# avr_pcb.net
KiCad netlist of a schematic drawn in EAGLE
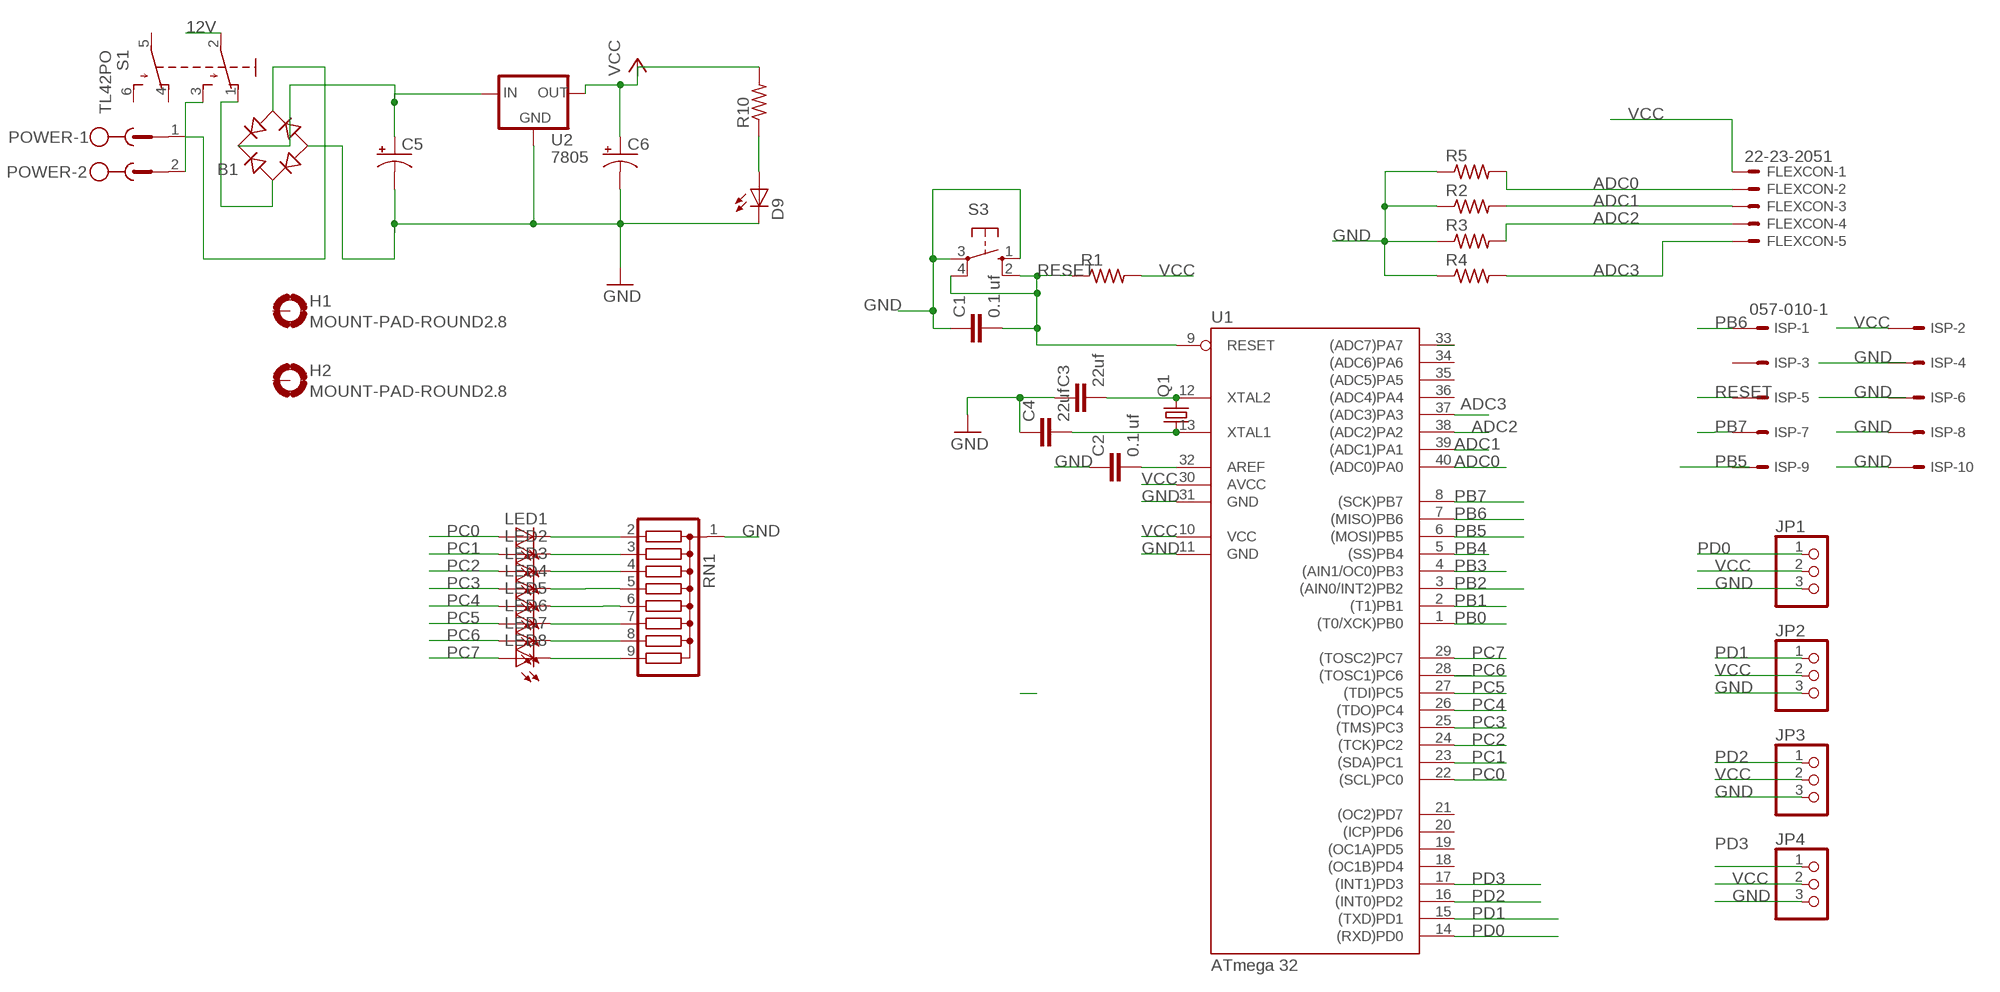
[diagram p0: schematic, sheet 1]

(export (version "E")
  (design (tool "Eeschema 10.0.6"))
  (components
    (comp (ref "B1")
      (value "RB1A")
      (footprint "eagle-import:RB1A")
      (libsource (lib "eagle-import") (part "RB1A"))
    )
    (comp (ref "C1")
      (value "0.1 uf")
      (footprint "eagle-import:C025-024X044")
      (libsource (lib "eagle-import") (part "C-EU025-024X044"))
    )
    (comp (ref "C2")
      (value "0.1 uf")
      (footprint "eagle-import:C025-024X044")
      (libsource (lib "eagle-import") (part "C-EU025-024X044"))
    )
    (comp (ref "C3")
      (value "22uf")
      (footprint "eagle-import:C025-024X044")
      (libsource (lib "eagle-import") (part "C-EU025-024X044"))
    )
    (comp (ref "C4")
      (value "22uf")
      (footprint "eagle-import:C025-024X044")
      (libsource (lib "eagle-import") (part "C-EU025-024X044"))
    )
    (comp (ref "C5")
      (value "CPOL-USE5-6")
      (footprint "eagle-import:E5-6")
      (libsource (lib "eagle-import") (part "CPOL-USE5-6"))
    )
    (comp (ref "C6")
      (value "CPOL-USE5-6")
      (footprint "eagle-import:E5-6")
      (libsource (lib "eagle-import") (part "CPOL-USE5-6"))
    )
    (comp (ref "D9")
      (value "LED3MM")
      (footprint "eagle-import:LED3MM")
      (libsource (lib "eagle-import") (part "LED3MM"))
    )
    (comp (ref "FLEXCON")
      (value "22-23-2051")
      (footprint "eagle-import:22-23-2051")
      (fields (field (name "MF") "MOLEX"))
      (libsource (lib "eagle-import") (part "22-23-2051"))
    )
    (comp (ref "H1")
      (value "MOUNT-PAD-ROUND2.8")
      (footprint "eagle-import:2,8-PAD")
      (libsource (lib "eagle-import") (part "MOUNT-PAD-ROUND2.8"))
    )
    (comp (ref "H2")
      (value "MOUNT-PAD-ROUND2.8")
      (footprint "eagle-import:2,8-PAD")
      (libsource (lib "eagle-import") (part "MOUNT-PAD-ROUND2.8"))
    )
    (comp (ref "ISP")
      (value "057-010-1")
      (footprint "eagle-import:057-010-1")
      (libsource (lib "eagle-import") (part "057-010-1"))
    )
    (comp (ref "JP1")
      (value "PINHD-1X3")
      (footprint "eagle-import:1X03")
      (fields (field (name "SPICEPREFIX") "J"))
      (libsource (lib "eagle-import") (part "PINHD-1X3"))
    )
    (comp (ref "JP2")
      (value "PINHD-1X3")
      (footprint "eagle-import:1X03")
      (libsource (lib "eagle-import") (part "PINHD-1X3"))
    )
    (comp (ref "JP3")
      (value "PINHD-1X3")
      (footprint "eagle-import:1X03")
      (libsource (lib "eagle-import") (part "PINHD-1X3"))
    )
    (comp (ref "JP4")
      (value "PINHD-1X3")
      (footprint "eagle-import:1X03")
      (libsource (lib "eagle-import") (part "PINHD-1X3"))
    )
    (comp (ref "LED1")
      (value "LED3MM")
      (footprint "eagle-import:LED3MM")
      (libsource (lib "eagle-import") (part "LED3MM"))
    )
    (comp (ref "LED2")
      (value "LED3MM")
      (footprint "eagle-import:LED3MM")
      (libsource (lib "eagle-import") (part "LED3MM"))
    )
    (comp (ref "LED3")
      (value "LED3MM")
      (footprint "eagle-import:LED3MM")
      (libsource (lib "eagle-import") (part "LED3MM"))
    )
    (comp (ref "LED4")
      (value "LED3MM")
      (footprint "eagle-import:LED3MM")
      (libsource (lib "eagle-import") (part "LED3MM"))
    )
    (comp (ref "LED5")
      (value "LED3MM")
      (footprint "eagle-import:LED3MM")
      (libsource (lib "eagle-import") (part "LED3MM"))
    )
    (comp (ref "LED6")
      (value "LED3MM")
      (footprint "eagle-import:LED3MM")
      (libsource (lib "eagle-import") (part "LED3MM"))
    )
    (comp (ref "LED7")
      (value "LED3MM")
      (footprint "eagle-import:LED3MM")
      (libsource (lib "eagle-import") (part "LED3MM"))
    )
    (comp (ref "LED8")
      (value "LED3MM")
      (footprint "eagle-import:LED3MM")
      (libsource (lib "eagle-import") (part "LED3MM"))
    )
    (comp (ref "POWER")
      (value "MSTBV2")
      (footprint "eagle-import:MSTBV2")
      (libsource (lib "eagle-import") (part "MSTBV2"))
    )
    (comp (ref "Q1")
      (value "CRYSTALHC18U-V")
      (footprint "eagle-import:HC18U-V")
      (libsource (lib "eagle-import") (part "CRYSTALHC18U-V"))
    )
    (comp (ref "R1")
      (value "R-US_0204/7")
      (footprint "eagle-import:0204_7")
      (libsource (lib "eagle-import") (part "R-US_0204/7"))
    )
    (comp (ref "R2")
      (value "R-US_0204/7")
      (footprint "eagle-import:0204_7")
      (libsource (lib "eagle-import") (part "R-US_0204/7"))
    )
    (comp (ref "R3")
      (value "R-US_0204/7")
      (footprint "eagle-import:0204_7")
      (libsource (lib "eagle-import") (part "R-US_0204/7"))
    )
    (comp (ref "R4")
      (value "R-US_0204/7")
      (footprint "eagle-import:0204_7")
      (libsource (lib "eagle-import") (part "R-US_0204/7"))
    )
    (comp (ref "R5")
      (value "R-US_0204/7")
      (footprint "eagle-import:0204_7")
      (libsource (lib "eagle-import") (part "R-US_0204/7"))
    )
    (comp (ref "R10")
      (value "R-US_0204/7")
      (footprint "eagle-import:0204_7")
      (libsource (lib "eagle-import") (part "R-US_0204/7"))
    )
    (comp (ref "RN1")
      (value "G08R")
      (footprint "eagle-import:SIL9")
      (libsource (lib "eagle-import") (part "G08R"))
    )
    (comp (ref "S1")
      (value "TL42PO")
      (footprint "eagle-import:TL4XPO")
      (libsource (lib "eagle-import") (part "TL42PO"))
    )
    (comp (ref "S3")
      (value "10-XX")
      (footprint "eagle-import:B3F-10XX")
      (fields (field (name "MPN") "B3F-1000"))
      (libsource (lib "eagle-import") (part "10-XX"))
    )
    (comp (ref "U1")
      (value "ATmega 32")
      (footprint "eagle-import:DIL40")
      (fields (field (name "MPN") "ATMEGA32-16PU"))
      (libsource (lib "eagle-import") (part "MEGA32-P"))
    )
    (comp (ref "U2")
      (value "7805")
      (footprint "eagle-import:78XXL")
      (libsource (lib "eagle-import") (part "78XXL"))
    )
  )
  (nets
    (net (code "1") (name "/12V") (class "Default")
      (node (ref "S1") (pin "2") (pinfunction "P_2") (pintype "passive"))
    )
    (net (code "2") (name "/ADC0") (class "Default")
      (node (ref "FLEXCON") (pin "2") (pinfunction "S_2") (pintype "passive"))
      (node (ref "R5") (pin "2") (pinfunction "2_2") (pintype "passive"))
      (node (ref "U1") (pin "40") (pinfunction "(ADC0)PA0_40") (pintype "bidirectional"))
    )
    (net (code "3") (name "/ADC1") (class "Default")
      (node (ref "FLEXCON") (pin "3") (pinfunction "S_3") (pintype "passive"))
      (node (ref "R2") (pin "2") (pinfunction "2_2") (pintype "passive"))
      (node (ref "U1") (pin "39") (pinfunction "(ADC1)PA1_39") (pintype "bidirectional"))
    )
    (net (code "4") (name "/ADC2") (class "Default")
      (node (ref "FLEXCON") (pin "4") (pinfunction "S_4") (pintype "passive"))
      (node (ref "R3") (pin "2") (pinfunction "2_2") (pintype "passive"))
      (node (ref "U1") (pin "38") (pinfunction "(ADC2)PA2_38") (pintype "bidirectional"))
    )
    (net (code "5") (name "/ADC3") (class "Default")
      (node (ref "FLEXCON") (pin "5") (pinfunction "S_5") (pintype "passive"))
      (node (ref "R4") (pin "2") (pinfunction "2_2") (pintype "passive"))
      (node (ref "U1") (pin "37") (pinfunction "(ADC3)PA3_37") (pintype "bidirectional"))
    )
    (net (code "6") (name "/PB0") (class "Default")
      (node (ref "U1") (pin "1") (pinfunction "(T0/XCK)PB0_1") (pintype "bidirectional"))
    )
    (net (code "7") (name "/PB1") (class "Default")
      (node (ref "U1") (pin "2") (pinfunction "(T1)PB1_2") (pintype "bidirectional"))
    )
    (net (code "8") (name "/PB2") (class "Default")
      (node (ref "U1") (pin "3") (pinfunction "(AIN0/INT2)PB2_3") (pintype "bidirectional"))
    )
    (net (code "9") (name "/PB3") (class "Default")
      (node (ref "U1") (pin "4") (pinfunction "(AIN1/OC0)PB3_4") (pintype "bidirectional"))
    )
    (net (code "10") (name "/PB4") (class "Default")
      (node (ref "U1") (pin "5") (pinfunction "(SS)PB4_5") (pintype "bidirectional"))
    )
    (net (code "11") (name "/PB5") (class "Default")
      (node (ref "ISP") (pin "9") (pinfunction "S_9") (pintype "passive"))
      (node (ref "U1") (pin "6") (pinfunction "(MOSI)PB5_6") (pintype "bidirectional"))
    )
    (net (code "12") (name "/PB6") (class "Default")
      (node (ref "ISP") (pin "1") (pinfunction "S_1") (pintype "passive"))
      (node (ref "U1") (pin "7") (pinfunction "(MISO)PB6_7") (pintype "bidirectional"))
    )
    (net (code "13") (name "/PB7") (class "Default")
      (node (ref "ISP") (pin "7") (pinfunction "S_7") (pintype "passive"))
      (node (ref "U1") (pin "8") (pinfunction "(SCK)PB7_8") (pintype "bidirectional"))
    )
    (net (code "14") (name "/PC0") (class "Default")
      (node (ref "LED1") (pin "A") (pinfunction "A_A") (pintype "passive"))
      (node (ref "U1") (pin "22") (pinfunction "(SCL)PC0_22") (pintype "bidirectional"))
    )
    (net (code "15") (name "/PC1") (class "Default")
      (node (ref "LED2") (pin "A") (pinfunction "A_A") (pintype "passive"))
      (node (ref "U1") (pin "23") (pinfunction "(SDA)PC1_23") (pintype "bidirectional"))
    )
    (net (code "16") (name "/PC2") (class "Default")
      (node (ref "LED3") (pin "A") (pinfunction "A_A") (pintype "passive"))
      (node (ref "U1") (pin "24") (pinfunction "(TCK)PC2_24") (pintype "bidirectional"))
    )
    (net (code "17") (name "/PC3") (class "Default")
      (node (ref "LED4") (pin "A") (pinfunction "A_A") (pintype "passive"))
      (node (ref "U1") (pin "25") (pinfunction "(TMS)PC3_25") (pintype "bidirectional"))
    )
    (net (code "18") (name "/PC4") (class "Default")
      (node (ref "LED5") (pin "A") (pinfunction "A_A") (pintype "passive"))
      (node (ref "U1") (pin "26") (pinfunction "(TDO)PC4_26") (pintype "bidirectional"))
    )
    (net (code "19") (name "/PC5") (class "Default")
      (node (ref "LED6") (pin "A") (pinfunction "A_A") (pintype "passive"))
      (node (ref "U1") (pin "27") (pinfunction "(TDI)PC5_27") (pintype "bidirectional"))
    )
    (net (code "20") (name "/PC6") (class "Default")
      (node (ref "LED7") (pin "A") (pinfunction "A_A") (pintype "passive"))
      (node (ref "U1") (pin "28") (pinfunction "(TOSC1)PC6_28") (pintype "bidirectional"))
    )
    (net (code "21") (name "/PC7") (class "Default")
      (node (ref "LED8") (pin "A") (pinfunction "A_A") (pintype "passive"))
      (node (ref "U1") (pin "29") (pinfunction "(TOSC2)PC7_29") (pintype "bidirectional"))
    )
    (net (code "22") (name "/PD0") (class "Default")
      (node (ref "JP1") (pin "1") (pinfunction "1_1") (pintype "passive"))
      (node (ref "U1") (pin "14") (pinfunction "(RXD)PD0_14") (pintype "bidirectional"))
    )
    (net (code "23") (name "/PD1") (class "Default")
      (node (ref "JP2") (pin "1") (pinfunction "1_1") (pintype "passive"))
      (node (ref "U1") (pin "15") (pinfunction "(TXD)PD1_15") (pintype "bidirectional"))
    )
    (net (code "24") (name "/PD2") (class "Default")
      (node (ref "JP3") (pin "1") (pinfunction "1_1") (pintype "passive"))
      (node (ref "U1") (pin "16") (pinfunction "(INT0)PD2_16") (pintype "bidirectional"))
    )
    (net (code "25") (name "/PD3") (class "Default")
      (node (ref "JP4") (pin "1") (pinfunction "1_1") (pintype "passive"))
      (node (ref "U1") (pin "17") (pinfunction "(INT1)PD3_17") (pintype "bidirectional"))
    )
    (net (code "26") (name "/RESET") (class "Default")
      (node (ref "C1") (pin "2") (pinfunction "2_2") (pintype "passive"))
      (node (ref "ISP") (pin "5") (pinfunction "S_5") (pintype "passive"))
      (node (ref "R1") (pin "1") (pinfunction "1_1") (pintype "passive"))
      (node (ref "S3") (pin "2") (pinfunction "S1_2") (pintype "passive"))
      (node (ref "S3") (pin "4") (pinfunction "P1_4") (pintype "passive"))
      (node (ref "U1") (pin "9") (pinfunction "RESET_9") (pintype "input"))
    )
    (net (code "27") (name "GND") (class "Default")
      (node (ref "B1") (pin "-") (pinfunction "-_-") (pintype "passive"))
      (node (ref "C1") (pin "1") (pinfunction "1_1") (pintype "passive"))
      (node (ref "C2") (pin "1") (pinfunction "1_1") (pintype "passive"))
      (node (ref "C3") (pin "1") (pinfunction "1_1") (pintype "passive"))
      (node (ref "C4") (pin "1") (pinfunction "1_1") (pintype "passive"))
      (node (ref "C5") (pin "-") (pinfunction "-_-") (pintype "passive"))
      (node (ref "C6") (pin "-") (pinfunction "-_-") (pintype "passive"))
      (node (ref "D9") (pin "K") (pinfunction "C_K") (pintype "passive"))
      (node (ref "ISP") (pin "10") (pinfunction "S_10") (pintype "passive"))
      (node (ref "ISP") (pin "4") (pinfunction "S_4") (pintype "passive"))
      (node (ref "ISP") (pin "6") (pinfunction "S_6") (pintype "passive"))
      (node (ref "ISP") (pin "8") (pinfunction "S_8") (pintype "passive"))
      (node (ref "JP1") (pin "3") (pinfunction "3_3") (pintype "passive"))
      (node (ref "JP2") (pin "3") (pinfunction "3_3") (pintype "passive"))
      (node (ref "JP3") (pin "3") (pinfunction "3_3") (pintype "passive"))
      (node (ref "JP4") (pin "3") (pinfunction "3_3") (pintype "passive"))
      (node (ref "R2") (pin "1") (pinfunction "1_1") (pintype "passive"))
      (node (ref "R3") (pin "1") (pinfunction "1_1") (pintype "passive"))
      (node (ref "R4") (pin "1") (pinfunction "1_1") (pintype "passive"))
      (node (ref "R5") (pin "1") (pinfunction "1_1") (pintype "passive"))
      (node (ref "RN1") (pin "1") (pinfunction "1_1") (pintype "passive"))
      (node (ref "S3") (pin "1") (pinfunction "S_1") (pintype "passive"))
      (node (ref "S3") (pin "3") (pinfunction "P_3") (pintype "passive"))
      (node (ref "U1") (pin "11") (pinfunction "GND_11") (pintype "power_in"))
      (node (ref "U1") (pin "31") (pinfunction "GND_31") (pintype "power_in"))
      (node (ref "U2") (pin "GND") (pinfunction "GND_GND") (pintype "input"))
    )
    (net (code "28") (name "Net-(B1-Pad+)") (class "Default")
      (node (ref "B1") (pin "+") (pinfunction "+_+") (pintype "passive"))
      (node (ref "C5") (pin "+") (pinfunction "+_+") (pintype "passive"))
      (node (ref "U2") (pin "IN") (pinfunction "IN_IN") (pintype "input"))
    )
    (net (code "29") (name "Net-(D9-PadA)") (class "Default")
      (node (ref "D9") (pin "A") (pinfunction "A_A") (pintype "passive"))
      (node (ref "R10") (pin "1") (pinfunction "1_1") (pintype "passive"))
    )
    (net (code "30") (name "Net-(LED1-C)") (class "Default")
      (node (ref "LED1") (pin "K") (pinfunction "C_K") (pintype "passive"))
      (node (ref "RN1") (pin "2") (pinfunction "2_2") (pintype "passive"))
    )
    (net (code "31") (name "Net-(LED2-C)") (class "Default")
      (node (ref "LED2") (pin "K") (pinfunction "C_K") (pintype "passive"))
      (node (ref "RN1") (pin "3") (pinfunction "3_3") (pintype "passive"))
    )
    (net (code "32") (name "Net-(LED3-C)") (class "Default")
      (node (ref "LED3") (pin "K") (pinfunction "C_K") (pintype "passive"))
      (node (ref "RN1") (pin "4") (pinfunction "4_4") (pintype "passive"))
    )
    (net (code "33") (name "Net-(LED4-C)") (class "Default")
      (node (ref "LED4") (pin "K") (pinfunction "C_K") (pintype "passive"))
      (node (ref "RN1") (pin "5") (pinfunction "5_5") (pintype "passive"))
    )
    (net (code "34") (name "Net-(LED5-C)") (class "Default")
      (node (ref "LED5") (pin "K") (pinfunction "C_K") (pintype "passive"))
      (node (ref "RN1") (pin "6") (pinfunction "6_6") (pintype "passive"))
    )
    (net (code "35") (name "Net-(LED6-C)") (class "Default")
      (node (ref "LED6") (pin "K") (pinfunction "C_K") (pintype "passive"))
      (node (ref "RN1") (pin "7") (pinfunction "7_7") (pintype "passive"))
    )
    (net (code "36") (name "Net-(LED7-C)") (class "Default")
      (node (ref "LED7") (pin "K") (pinfunction "C_K") (pintype "passive"))
      (node (ref "RN1") (pin "8") (pinfunction "8_8") (pintype "passive"))
    )
    (net (code "37") (name "Net-(LED8-C)") (class "Default")
      (node (ref "LED8") (pin "K") (pinfunction "C_K") (pintype "passive"))
      (node (ref "RN1") (pin "9") (pinfunction "9_9") (pintype "passive"))
    )
    (net (code "38") (name "Net-(POWERA-SK)") (class "Default")
      (node (ref "B1") (pin "AC2") (pinfunction "AC2_AC2") (pintype "passive"))
      (node (ref "POWER") (pin "1") (pinfunction "SK_1") (pintype "passive"))
    )
    (net (code "39") (name "Net-(POWERB-SK)") (class "Default")
      (node (ref "POWER") (pin "2") (pinfunction "SK_2") (pintype "passive"))
      (node (ref "S1") (pin "3") (pinfunction "S_3") (pintype "passive"))
    )
    (net (code "40") (name "Net-(S1-O)") (class "Default")
      (node (ref "B1") (pin "AC1") (pinfunction "AC1_AC1") (pintype "passive"))
      (node (ref "S1") (pin "1") (pinfunction "O_1") (pintype "passive"))
    )
    (net (code "41") (name "Net-(U1-AREF)") (class "Default")
      (node (ref "C2") (pin "2") (pinfunction "2_2") (pintype "passive"))
      (node (ref "U1") (pin "32") (pinfunction "AREF_32") (pintype "passive"))
    )
    (net (code "42") (name "Net-(U1-XTAL1)") (class "Default")
      (node (ref "C4") (pin "2") (pinfunction "2_2") (pintype "passive"))
      (node (ref "Q1") (pin "1") (pinfunction "1_1") (pintype "passive"))
      (node (ref "U1") (pin "13") (pinfunction "XTAL1_13") (pintype "bidirectional"))
    )
    (net (code "43") (name "Net-(U1-XTAL2)") (class "Default")
      (node (ref "C3") (pin "2") (pinfunction "2_2") (pintype "passive"))
      (node (ref "Q1") (pin "2") (pinfunction "2_2") (pintype "passive"))
      (node (ref "U1") (pin "12") (pinfunction "XTAL2_12") (pintype "bidirectional"))
    )
    (net (code "44") (name "VCC") (class "Default")
      (node (ref "C6") (pin "+") (pinfunction "+_+") (pintype "passive"))
      (node (ref "FLEXCON") (pin "1") (pinfunction "S_1") (pintype "passive"))
      (node (ref "ISP") (pin "2") (pinfunction "S_2") (pintype "passive"))
      (node (ref "JP1") (pin "2") (pinfunction "2_2") (pintype "passive"))
      (node (ref "JP2") (pin "2") (pinfunction "2_2") (pintype "passive"))
      (node (ref "JP3") (pin "2") (pinfunction "2_2") (pintype "passive"))
      (node (ref "JP4") (pin "2") (pinfunction "2_2") (pintype "passive"))
      (node (ref "R1") (pin "2") (pinfunction "2_2") (pintype "passive"))
      (node (ref "R10") (pin "2") (pinfunction "2_2") (pintype "passive"))
      (node (ref "U1") (pin "10") (pinfunction "VCC_10") (pintype "power_in"))
      (node (ref "U1") (pin "30") (pinfunction "AVCC_30") (pintype "power_in"))
      (node (ref "U2") (pin "OUT") (pinfunction "OUT_OUT") (pintype "passive"))
    )
    (net (code "45") (name "unconnected-(H1-MOUNT-PadB2,8)") (class "Default")
      (node (ref "H1") (pin "B2,8") (pinfunction "MOUNT_B2,8") (pintype "passive"))
    )
    (net (code "46") (name "unconnected-(H2-MOUNT-PadB2,8)") (class "Default")
      (node (ref "H2") (pin "B2,8") (pinfunction "MOUNT_B2,8") (pintype "passive"))
    )
    (net (code "47") (name "unconnected-(ISPD-S-Pad3)") (class "Default")
      (node (ref "ISP") (pin "3") (pinfunction "S_3") (pintype "passive"))
    )
    (net (code "48") (name "unconnected-(S1-O1-Pad4)") (class "Default")
      (node (ref "S1") (pin "4") (pinfunction "O1_4") (pintype "passive"))
    )
    (net (code "49") (name "unconnected-(S1-P1-Pad5)") (class "Default")
      (node (ref "S1") (pin "5") (pinfunction "P1_5") (pintype "passive"))
    )
    (net (code "50") (name "unconnected-(S1-S1-Pad6)") (class "Default")
      (node (ref "S1") (pin "6") (pinfunction "S1_6") (pintype "passive"))
    )
    (net (code "51") (name "unconnected-(U1-(ADC4)PA4-Pad36)") (class "Default")
      (node (ref "U1") (pin "36") (pinfunction "(ADC4)PA4_36") (pintype "bidirectional"))
    )
    (net (code "52") (name "unconnected-(U1-(ADC5)PA5-Pad35)") (class "Default")
      (node (ref "U1") (pin "35") (pinfunction "(ADC5)PA5_35") (pintype "bidirectional"))
    )
    (net (code "53") (name "unconnected-(U1-(ADC6)PA6-Pad34)") (class "Default")
      (node (ref "U1") (pin "34") (pinfunction "(ADC6)PA6_34") (pintype "bidirectional"))
    )
    (net (code "54") (name "unconnected-(U1-(ADC7)PA7-Pad33)") (class "Default")
      (node (ref "U1") (pin "33") (pinfunction "(ADC7)PA7_33") (pintype "bidirectional"))
    )
    (net (code "55") (name "unconnected-(U1-(ICP)PD6-Pad20)") (class "Default")
      (node (ref "U1") (pin "20") (pinfunction "(ICP)PD6_20") (pintype "bidirectional"))
    )
    (net (code "56") (name "unconnected-(U1-(OC1A)PD5-Pad19)") (class "Default")
      (node (ref "U1") (pin "19") (pinfunction "(OC1A)PD5_19") (pintype "bidirectional"))
    )
    (net (code "57") (name "unconnected-(U1-(OC1B)PD4-Pad18)") (class "Default")
      (node (ref "U1") (pin "18") (pinfunction "(OC1B)PD4_18") (pintype "bidirectional"))
    )
    (net (code "58") (name "unconnected-(U1-(OC2)PD7-Pad21)") (class "Default")
      (node (ref "U1") (pin "21") (pinfunction "(OC2)PD7_21") (pintype "bidirectional"))
    )
  )
)
